# ID_logic.net
KiCad netlist of a schematic drawn in Altium Designer
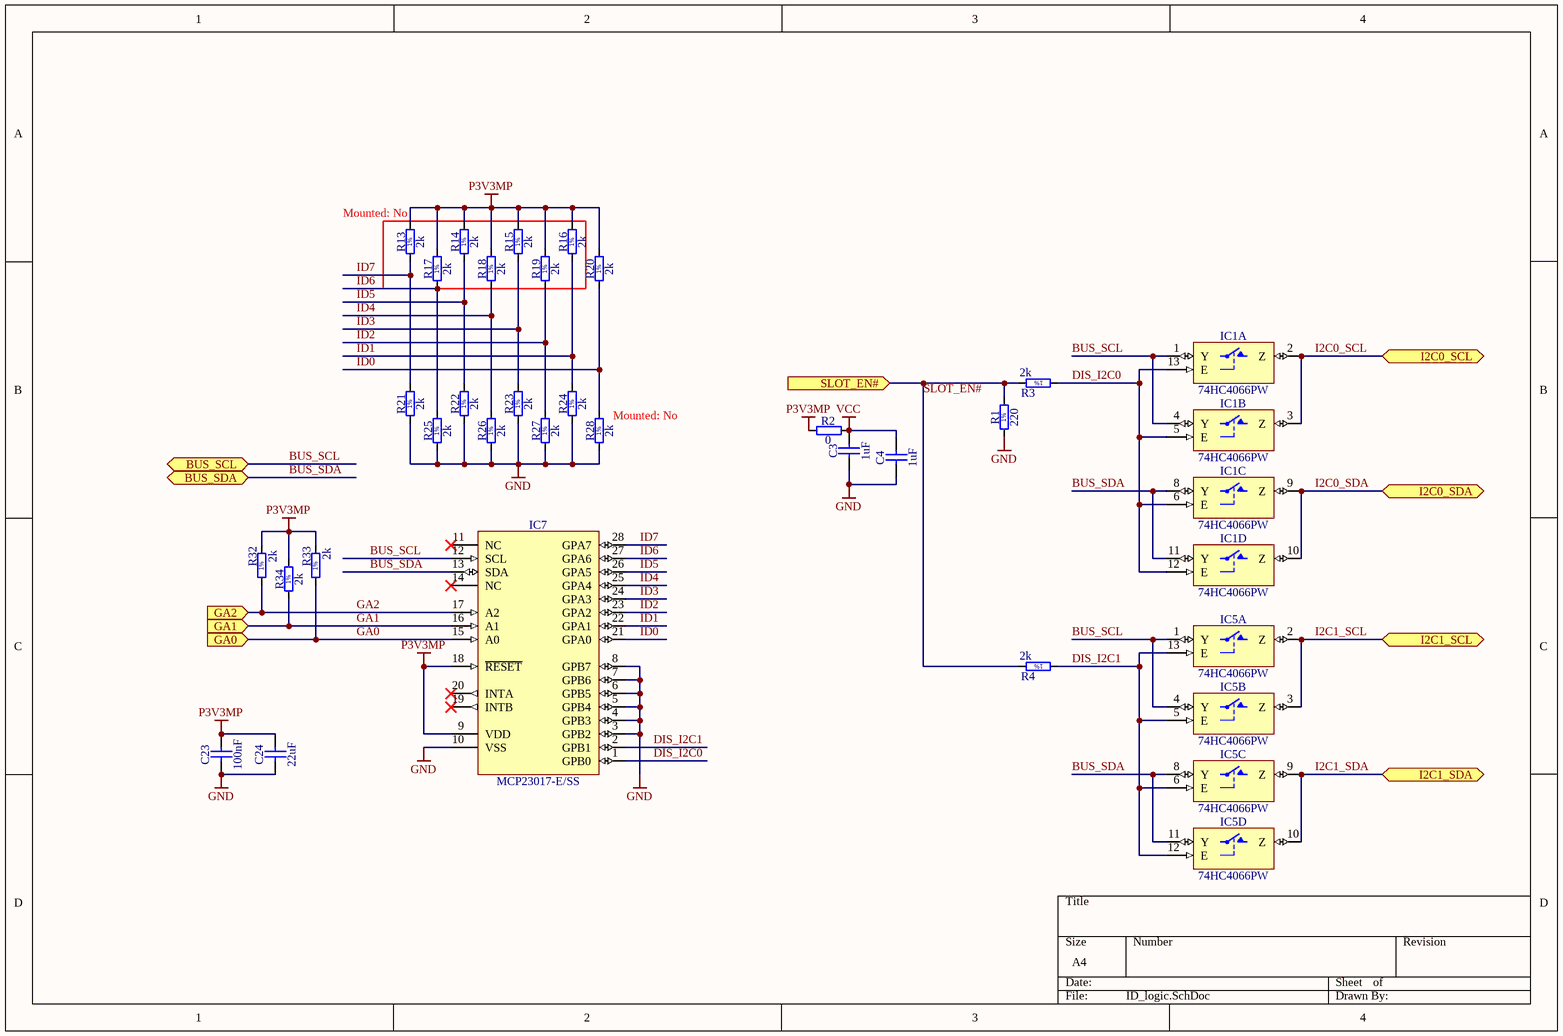
[diagram p0: ID_logic.SchDoc]

(export (version "E")
  (design (tool "Eeschema 10.0.6"))
  (components
    (comp (ref "C3")
      (value "1uF")
      (footprint "CAPC2012X140N")
      (description "Non-polarised capacitor")
      (fields
        (field (name "PART NUMBER") "CC0805_1UF_35V_20%_X7R")
        (field (name "VOLTAGE") "35V")
        (field (name "AUTHOR") "CERN DEM JLC")
      )
      (libsource (lib "Capacitors") (part "Capacitor - non polarized"))
    )
    (comp (ref "C4")
      (value "1uF")
      (footprint "CAPC2012X140N")
      (description "Non-polarised capacitor")
      (fields
        (field (name "PART NUMBER") "CC0805_1UF_35V_20%_X7R")
        (field (name "VOLTAGE") "35V")
        (field (name "AUTHOR") "CERN DEM JLC")
      )
      (libsource (lib "Capacitors") (part "Capacitor - non polarized"))
    )
    (comp (ref "C23")
      (value "100nF")
      (footprint "CAPC3216X140N")
      (description "Non-polarised capacitor")
      (fields
        (field (name "PART NUMBER") "CC1206_100NF_50V_10%_X7R")
        (field (name "VOLTAGE") "50V")
        (field (name "AUTHOR") "CERN DEM JLC")
      )
      (libsource (lib "Capacitors") (part "Capacitor - non polarized"))
    )
    (comp (ref "C24")
      (value "22uF")
      (footprint "CAPC3216X180N")
      (description "Non-polarised capacitor")
      (fields
        (field (name "PART NUMBER") "CC1206_22UF_35V_20%_JB_TDK_C3216JB1V226M160AC")
        (field (name "VOLTAGE") "35V")
        (field (name "AUTHOR") "CERN DEM JLC")
      )
      (libsource (lib "Capacitors") (part "Capacitor - non polarized"))
    )
    (comp (ref "IC1")
      (value "74HC4066PW")
      (footprint "SOP65P640X110-14N")
      (fields (field (name "MANUFACTURER") "NXP SEMICONDUCTORS") (field (name "AUTHOR") "CERN DEM JLC"))
      (libsource (lib "ICs And Semiconductors") (part "4066"))
    )
    (comp (ref "IC5")
      (value "74HC4066PW")
      (footprint "SOP65P640X110-14N")
      (fields (field (name "MANUFACTURER") "NXP SEMICONDUCTORS") (field (name "AUTHOR") "CERN DEM JLC"))
      (libsource (lib "ICs And Semiconductors") (part "4066"))
    )
    (comp (ref "IC7")
      (value "MCP23017-E/SS")
      (footprint "SOP65P780X200-28N")
      (description "16-bit I/O Port Expander With Serial Interface")
      (fields (field (name "MANUFACTURER") "MICROCHIP TECHNOLOGY") (field (name "AUTHOR") "CERN DEM JLC"))
      (libsource (lib "ICs And Semiconductors") (part "MCP23017-E/SS"))
    )
    (comp (ref "R1")
      (value "220")
      (footprint "RESC1608X55N")
      (description "Resistor - 1%")
      (fields
        (field (name "PART NUMBER") "R0603_220R_1%_0.1W_100PPM")
        (field (name "POWER") "0.1W")
        (field (name "AUTHOR") "CERN DEM JLC")
      )
      (libsource (lib "Resistors") (part "Resistor - 1%"))
    )
    (comp (ref "R2")
      (value "0")
      (footprint "RESC1005X40N")
      (description "Resistor")
      (fields
        (field (name "PART NUMBER") "R0402_0R_JUMPER")
        (field (name "MANUFACTURER") "GENERIC")
        (field (name "AUTHOR") "CERN DEM JLC")
      )
      (libsource (lib "Resistors") (part "Resistor"))
    )
    (comp (ref "R3")
      (value "2k")
      (footprint "RESC1608X55N")
      (description "Resistor - 1%")
      (fields
        (field (name "PART NUMBER") "R0603_2K_1%_0.1W_100PPM")
        (field (name "POWER") "0.1W")
        (field (name "AUTHOR") "CERN DEM JLC")
      )
      (libsource (lib "Resistors") (part "Resistor - 1%"))
    )
    (comp (ref "R4")
      (value "2k")
      (footprint "RESC1608X55N")
      (description "Resistor - 1%")
      (fields
        (field (name "PART NUMBER") "R0603_2K_1%_0.1W_100PPM")
        (field (name "POWER") "0.1W")
        (field (name "AUTHOR") "CERN DEM JLC")
      )
      (libsource (lib "Resistors") (part "Resistor - 1%"))
    )
    (comp (ref "R13")
      (value "2k")
      (footprint "RESC1608X55N")
      (description "Resistor - 1%")
      (fields
        (field (name "PART NUMBER") "R0603_2K_1%_0.1W_100PPM")
        (field (name "POWER") "0.1W")
        (field (name "MOUNTED") "No")
        (field (name "AUTHOR") "CERN DEM JLC")
      )
      (libsource (lib "Resistors") (part "Resistor - 1%"))
    )
    (comp (ref "R14")
      (value "2k")
      (footprint "RESC1608X55N")
      (description "Resistor - 1%")
      (fields
        (field (name "PART NUMBER") "R0603_2K_1%_0.1W_100PPM")
        (field (name "POWER") "0.1W")
        (field (name "AUTHOR") "CERN DEM JLC")
      )
      (libsource (lib "Resistors") (part "Resistor - 1%"))
    )
    (comp (ref "R15")
      (value "2k")
      (footprint "RESC1608X55N")
      (description "Resistor - 1%")
      (fields
        (field (name "PART NUMBER") "R0603_2K_1%_0.1W_100PPM")
        (field (name "POWER") "0.1W")
        (field (name "AUTHOR") "CERN DEM JLC")
      )
      (libsource (lib "Resistors") (part "Resistor - 1%"))
    )
    (comp (ref "R16")
      (value "2k")
      (footprint "RESC1608X55N")
      (description "Resistor - 1%")
      (fields
        (field (name "PART NUMBER") "R0603_2K_1%_0.1W_100PPM")
        (field (name "POWER") "0.1W")
        (field (name "AUTHOR") "CERN DEM JLC")
      )
      (libsource (lib "Resistors") (part "Resistor - 1%"))
    )
    (comp (ref "R17")
      (value "2k")
      (footprint "RESC1608X55N")
      (description "Resistor - 1%")
      (fields
        (field (name "PART NUMBER") "R0603_2K_1%_0.1W_100PPM")
        (field (name "POWER") "0.1W")
        (field (name "AUTHOR") "CERN DEM JLC")
      )
      (libsource (lib "Resistors") (part "Resistor - 1%"))
    )
    (comp (ref "R18")
      (value "2k")
      (footprint "RESC1608X55N")
      (description "Resistor - 1%")
      (fields
        (field (name "PART NUMBER") "R0603_2K_1%_0.1W_100PPM")
        (field (name "POWER") "0.1W")
        (field (name "AUTHOR") "CERN DEM JLC")
      )
      (libsource (lib "Resistors") (part "Resistor - 1%"))
    )
    (comp (ref "R19")
      (value "2k")
      (footprint "RESC1608X55N")
      (description "Resistor - 1%")
      (fields
        (field (name "PART NUMBER") "R0603_2K_1%_0.1W_100PPM")
        (field (name "POWER") "0.1W")
        (field (name "AUTHOR") "CERN DEM JLC")
      )
      (libsource (lib "Resistors") (part "Resistor - 1%"))
    )
    (comp (ref "R20")
      (value "2k")
      (footprint "RESC1608X55N")
      (description "Resistor - 1%")
      (fields
        (field (name "PART NUMBER") "R0603_2K_1%_0.1W_100PPM")
        (field (name "POWER") "0.1W")
        (field (name "AUTHOR") "CERN DEM JLC")
      )
      (libsource (lib "Resistors") (part "Resistor - 1%"))
    )
    (comp (ref "R21")
      (value "2k")
      (footprint "RESC1608X55N")
      (description "Resistor - 1%")
      (fields
        (field (name "PART NUMBER") "R0603_2K_1%_0.1W_100PPM")
        (field (name "POWER") "0.1W")
        (field (name "AUTHOR") "CERN DEM JLC")
      )
      (libsource (lib "Resistors") (part "Resistor - 1%"))
    )
    (comp (ref "R22")
      (value "2k")
      (footprint "RESC1608X55N")
      (description "Resistor - 1%")
      (fields
        (field (name "PART NUMBER") "R0603_2K_1%_0.1W_100PPM")
        (field (name "POWER") "0.1W")
        (field (name "AUTHOR") "CERN DEM JLC")
      )
      (libsource (lib "Resistors") (part "Resistor - 1%"))
    )
    (comp (ref "R23")
      (value "2k")
      (footprint "RESC1608X55N")
      (description "Resistor - 1%")
      (fields
        (field (name "PART NUMBER") "R0603_2K_1%_0.1W_100PPM")
        (field (name "POWER") "0.1W")
        (field (name "AUTHOR") "CERN DEM JLC")
      )
      (libsource (lib "Resistors") (part "Resistor - 1%"))
    )
    (comp (ref "R24")
      (value "2k")
      (footprint "RESC1608X55N")
      (description "Resistor - 1%")
      (fields
        (field (name "PART NUMBER") "R0603_2K_1%_0.1W_100PPM")
        (field (name "POWER") "0.1W")
        (field (name "AUTHOR") "CERN DEM JLC")
      )
      (libsource (lib "Resistors") (part "Resistor - 1%"))
    )
    (comp (ref "R25")
      (value "2k")
      (footprint "RESC1608X55N")
      (description "Resistor - 1%")
      (fields
        (field (name "PART NUMBER") "R0603_2K_1%_0.1W_100PPM")
        (field (name "POWER") "0.1W")
        (field (name "AUTHOR") "CERN DEM JLC")
      )
      (libsource (lib "Resistors") (part "Resistor - 1%"))
    )
    (comp (ref "R26")
      (value "2k")
      (footprint "RESC1608X55N")
      (description "Resistor - 1%")
      (fields
        (field (name "PART NUMBER") "R0603_2K_1%_0.1W_100PPM")
        (field (name "POWER") "0.1W")
        (field (name "AUTHOR") "CERN DEM JLC")
      )
      (libsource (lib "Resistors") (part "Resistor - 1%"))
    )
    (comp (ref "R27")
      (value "2k")
      (footprint "RESC1608X55N")
      (description "Resistor - 1%")
      (fields
        (field (name "PART NUMBER") "R0603_2K_1%_0.1W_100PPM")
        (field (name "POWER") "0.1W")
        (field (name "AUTHOR") "CERN DEM JLC")
      )
      (libsource (lib "Resistors") (part "Resistor - 1%"))
    )
    (comp (ref "R28")
      (value "2k")
      (footprint "RESC1608X55N")
      (description "Resistor - 1%")
      (fields
        (field (name "PART NUMBER") "R0603_2K_1%_0.1W_100PPM")
        (field (name "POWER") "0.1W")
        (field (name "MOUNTED") "No")
        (field (name "AUTHOR") "CERN DEM JLC")
      )
      (libsource (lib "Resistors") (part "Resistor - 1%"))
    )
    (comp (ref "R32")
      (value "2k")
      (footprint "RESC1608X55N")
      (description "Resistor - 1%")
      (fields
        (field (name "PART NUMBER") "R0603_2K_1%_0.1W_100PPM")
        (field (name "POWER") "0.1W")
        (field (name "AUTHOR") "CERN DEM JLC")
      )
      (libsource (lib "Resistors") (part "Resistor - 1%"))
    )
    (comp (ref "R33")
      (value "2k")
      (footprint "RESC1608X55N")
      (description "Resistor - 1%")
      (fields
        (field (name "PART NUMBER") "R0603_2K_1%_0.1W_100PPM")
        (field (name "POWER") "0.1W")
        (field (name "AUTHOR") "CERN DEM JLC")
      )
      (libsource (lib "Resistors") (part "Resistor - 1%"))
    )
    (comp (ref "R34")
      (value "2k")
      (footprint "RESC1608X55N")
      (description "Resistor - 1%")
      (fields
        (field (name "PART NUMBER") "R0603_2K_1%_0.1W_100PPM")
        (field (name "POWER") "0.1W")
        (field (name "AUTHOR") "CERN DEM JLC")
      )
      (libsource (lib "Resistors") (part "Resistor - 1%"))
    )
  )
  (nets
    (net (code "1") (name "/BUS_SCL") (class "Default")
      (node (ref "IC1") (pin "1") (pinfunction "Y_1") (pintype "bidirectional"))
      (node (ref "IC1") (pin "4") (pinfunction "Y_4") (pintype "bidirectional"))
      (node (ref "IC5") (pin "1") (pinfunction "Y_1") (pintype "bidirectional"))
      (node (ref "IC5") (pin "4") (pinfunction "Y_4") (pintype "bidirectional"))
      (node (ref "IC7") (pin "12") (pinfunction "SCL_12") (pintype "input"))
    )
    (net (code "2") (name "/BUS_SDA") (class "Default")
      (node (ref "IC1") (pin "11") (pinfunction "Y_11") (pintype "bidirectional"))
      (node (ref "IC1") (pin "8") (pinfunction "Y_8") (pintype "bidirectional"))
      (node (ref "IC5") (pin "11") (pinfunction "Y_11") (pintype "bidirectional"))
      (node (ref "IC5") (pin "8") (pinfunction "Y_8") (pintype "bidirectional"))
      (node (ref "IC7") (pin "13") (pinfunction "SDA_13") (pintype "bidirectional"))
    )
    (net (code "3") (name "/DIS_I2C0") (class "Default")
      (node (ref "IC1") (pin "12") (pinfunction "E_12") (pintype "input"))
      (node (ref "IC1") (pin "13") (pinfunction "E_13") (pintype "input"))
      (node (ref "IC1") (pin "5") (pinfunction "E_5") (pintype "input"))
      (node (ref "IC1") (pin "6") (pinfunction "E_6") (pintype "input"))
      (node (ref "IC7") (pin "1") (pinfunction "GPB0_1") (pintype "bidirectional"))
      (node (ref "R3") (pin "1") (pinfunction "1_1") (pintype "passive"))
    )
    (net (code "4") (name "/DIS_I2C1") (class "Default")
      (node (ref "IC5") (pin "12") (pinfunction "E_12") (pintype "input"))
      (node (ref "IC5") (pin "13") (pinfunction "E_13") (pintype "input"))
      (node (ref "IC5") (pin "5") (pinfunction "E_5") (pintype "input"))
      (node (ref "IC5") (pin "6") (pinfunction "E_6") (pintype "input"))
      (node (ref "IC7") (pin "2") (pinfunction "GPB1_2") (pintype "bidirectional"))
      (node (ref "R4") (pin "1") (pinfunction "1_1") (pintype "passive"))
    )
    (net (code "5") (name "/GA0") (class "Default")
      (node (ref "IC7") (pin "15") (pinfunction "A0_15") (pintype "input"))
      (node (ref "R33") (pin "1") (pinfunction "1_1") (pintype "passive"))
    )
    (net (code "6") (name "/GA1") (class "Default")
      (node (ref "IC7") (pin "16") (pinfunction "A1_16") (pintype "input"))
      (node (ref "R34") (pin "1") (pinfunction "1_1") (pintype "passive"))
    )
    (net (code "7") (name "/GA2") (class "Default")
      (node (ref "IC7") (pin "17") (pinfunction "A2_17") (pintype "input"))
      (node (ref "R32") (pin "1") (pinfunction "1_1") (pintype "passive"))
    )
    (net (code "8") (name "/I2C0_SCL") (class "Default")
      (node (ref "IC1") (pin "2") (pinfunction "Z_2") (pintype "bidirectional"))
      (node (ref "IC1") (pin "3") (pinfunction "Z_3") (pintype "bidirectional"))
    )
    (net (code "9") (name "/I2C0_SDA") (class "Default")
      (node (ref "IC1") (pin "10") (pinfunction "Z_10") (pintype "bidirectional"))
      (node (ref "IC1") (pin "9") (pinfunction "Z_9") (pintype "bidirectional"))
    )
    (net (code "10") (name "/I2C1_SCL") (class "Default")
      (node (ref "IC5") (pin "2") (pinfunction "Z_2") (pintype "bidirectional"))
      (node (ref "IC5") (pin "3") (pinfunction "Z_3") (pintype "bidirectional"))
    )
    (net (code "11") (name "/I2C1_SDA") (class "Default")
      (node (ref "IC5") (pin "10") (pinfunction "Z_10") (pintype "bidirectional"))
      (node (ref "IC5") (pin "9") (pinfunction "Z_9") (pintype "bidirectional"))
    )
    (net (code "12") (name "/ID0") (class "Default")
      (node (ref "IC7") (pin "21") (pinfunction "GPA0_21") (pintype "bidirectional"))
      (node (ref "R20") (pin "1") (pinfunction "1_1") (pintype "passive"))
      (node (ref "R28") (pin "2") (pinfunction "2_2") (pintype "passive"))
    )
    (net (code "13") (name "/ID1") (class "Default")
      (node (ref "IC7") (pin "22") (pinfunction "GPA1_22") (pintype "bidirectional"))
      (node (ref "R16") (pin "1") (pinfunction "1_1") (pintype "passive"))
      (node (ref "R24") (pin "2") (pinfunction "2_2") (pintype "passive"))
    )
    (net (code "14") (name "/ID2") (class "Default")
      (node (ref "IC7") (pin "23") (pinfunction "GPA2_23") (pintype "bidirectional"))
      (node (ref "R19") (pin "1") (pinfunction "1_1") (pintype "passive"))
      (node (ref "R27") (pin "2") (pinfunction "2_2") (pintype "passive"))
    )
    (net (code "15") (name "/ID3") (class "Default")
      (node (ref "IC7") (pin "24") (pinfunction "GPA3_24") (pintype "bidirectional"))
      (node (ref "R15") (pin "1") (pinfunction "1_1") (pintype "passive"))
      (node (ref "R23") (pin "2") (pinfunction "2_2") (pintype "passive"))
    )
    (net (code "16") (name "/ID4") (class "Default")
      (node (ref "IC7") (pin "25") (pinfunction "GPA4_25") (pintype "bidirectional"))
      (node (ref "R18") (pin "1") (pinfunction "1_1") (pintype "passive"))
      (node (ref "R26") (pin "2") (pinfunction "2_2") (pintype "passive"))
    )
    (net (code "17") (name "/ID5") (class "Default")
      (node (ref "IC7") (pin "26") (pinfunction "GPA5_26") (pintype "bidirectional"))
      (node (ref "R14") (pin "1") (pinfunction "1_1") (pintype "passive"))
      (node (ref "R22") (pin "2") (pinfunction "2_2") (pintype "passive"))
    )
    (net (code "18") (name "/ID6") (class "Default")
      (node (ref "IC7") (pin "27") (pinfunction "GPA6_27") (pintype "bidirectional"))
      (node (ref "R17") (pin "1") (pinfunction "1_1") (pintype "passive"))
      (node (ref "R25") (pin "2") (pinfunction "2_2") (pintype "passive"))
    )
    (net (code "19") (name "/ID7") (class "Default")
      (node (ref "IC7") (pin "28") (pinfunction "GPA7_28") (pintype "bidirectional"))
      (node (ref "R13") (pin "1") (pinfunction "1_1") (pintype "passive"))
      (node (ref "R21") (pin "2") (pinfunction "2_2") (pintype "passive"))
    )
    (net (code "20") (name "/SLOT_EN#") (class "Default")
      (node (ref "R1") (pin "2") (pinfunction "2_2") (pintype "passive"))
      (node (ref "R3") (pin "2") (pinfunction "2_2") (pintype "passive"))
      (node (ref "R4") (pin "2") (pinfunction "2_2") (pintype "passive"))
    )
    (net (code "21") (name "GND") (class "Default")
      (node (ref "C23") (pin "1") (pinfunction "1_1") (pintype "passive"))
      (node (ref "C24") (pin "1") (pinfunction "1_1") (pintype "passive"))
      (node (ref "C3") (pin "1") (pinfunction "1_1") (pintype "passive"))
      (node (ref "C4") (pin "1") (pinfunction "1_1") (pintype "passive"))
      (node (ref "IC1") (pin "7") (pinfunction "GND_7") (pintype "power_in"))
      (node (ref "IC5") (pin "7") (pinfunction "GND_7") (pintype "power_in"))
      (node (ref "IC7") (pin "10") (pinfunction "VSS_10") (pintype "power_in"))
      (node (ref "IC7") (pin "3") (pinfunction "GPB2_3") (pintype "bidirectional"))
      (node (ref "IC7") (pin "4") (pinfunction "GPB3_4") (pintype "bidirectional"))
      (node (ref "IC7") (pin "5") (pinfunction "GPB4_5") (pintype "bidirectional"))
      (node (ref "IC7") (pin "6") (pinfunction "GPB5_6") (pintype "bidirectional"))
      (node (ref "IC7") (pin "7") (pinfunction "GPB6_7") (pintype "bidirectional"))
      (node (ref "IC7") (pin "8") (pinfunction "GPB7_8") (pintype "bidirectional"))
      (node (ref "R1") (pin "1") (pinfunction "1_1") (pintype "passive"))
      (node (ref "R21") (pin "1") (pinfunction "1_1") (pintype "passive"))
      (node (ref "R22") (pin "1") (pinfunction "1_1") (pintype "passive"))
      (node (ref "R23") (pin "1") (pinfunction "1_1") (pintype "passive"))
      (node (ref "R24") (pin "1") (pinfunction "1_1") (pintype "passive"))
      (node (ref "R25") (pin "1") (pinfunction "1_1") (pintype "passive"))
      (node (ref "R26") (pin "1") (pinfunction "1_1") (pintype "passive"))
      (node (ref "R27") (pin "1") (pinfunction "1_1") (pintype "passive"))
      (node (ref "R28") (pin "1") (pinfunction "1_1") (pintype "passive"))
    )
    (net (code "22") (name "P3V3MP") (class "Default")
      (node (ref "C23") (pin "2") (pinfunction "2_2") (pintype "passive"))
      (node (ref "C24") (pin "2") (pinfunction "2_2") (pintype "passive"))
      (node (ref "IC7") (pin "18") (pinfunction "~{RESET}_18") (pintype "input"))
      (node (ref "IC7") (pin "9") (pinfunction "VDD_9") (pintype "power_in"))
      (node (ref "R13") (pin "2") (pinfunction "2_2") (pintype "passive"))
      (node (ref "R14") (pin "2") (pinfunction "2_2") (pintype "passive"))
      (node (ref "R15") (pin "2") (pinfunction "2_2") (pintype "passive"))
      (node (ref "R16") (pin "2") (pinfunction "2_2") (pintype "passive"))
      (node (ref "R17") (pin "2") (pinfunction "2_2") (pintype "passive"))
      (node (ref "R18") (pin "2") (pinfunction "2_2") (pintype "passive"))
      (node (ref "R19") (pin "2") (pinfunction "2_2") (pintype "passive"))
      (node (ref "R2") (pin "1") (pinfunction "1_1") (pintype "passive"))
      (node (ref "R20") (pin "2") (pinfunction "2_2") (pintype "passive"))
      (node (ref "R32") (pin "2") (pinfunction "2_2") (pintype "passive"))
      (node (ref "R33") (pin "2") (pinfunction "2_2") (pintype "passive"))
      (node (ref "R34") (pin "2") (pinfunction "2_2") (pintype "passive"))
    )
    (net (code "23") (name "VCC") (class "Default")
      (node (ref "C3") (pin "2") (pinfunction "2_2") (pintype "passive"))
      (node (ref "C4") (pin "2") (pinfunction "2_2") (pintype "passive"))
      (node (ref "IC1") (pin "14") (pinfunction "VCC_14") (pintype "power_in"))
      (node (ref "IC5") (pin "14") (pinfunction "VCC_14") (pintype "power_in"))
      (node (ref "R2") (pin "2") (pinfunction "2_2") (pintype "passive"))
    )
    (net (code "24") (name "unconnected-(IC7-INTA-Pad20)") (class "Default")
      (node (ref "IC7") (pin "20") (pinfunction "INTA_20") (pintype "output+no_connect"))
    )
    (net (code "25") (name "unconnected-(IC7-INTB-Pad19)") (class "Default")
      (node (ref "IC7") (pin "19") (pinfunction "INTB_19") (pintype "output+no_connect"))
    )
    (net (code "26") (name "unconnected-(IC7-NC-Pad11)") (class "Default")
      (node (ref "IC7") (pin "11") (pinfunction "NC_11") (pintype "passive+no_connect"))
    )
    (net (code "27") (name "unconnected-(IC7-NC-Pad14)") (class "Default")
      (node (ref "IC7") (pin "14") (pinfunction "NC_14") (pintype "passive+no_connect"))
    )
  )
)
